# type_2_signaling.net
KiCad netlist of a schematic drawn in EAGLE
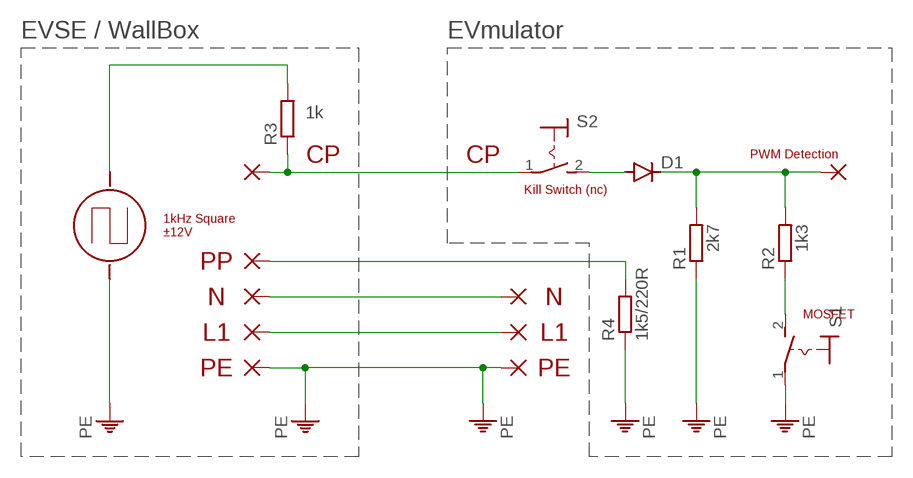
[diagram p0: schematic, sheet 1]

(export (version "E")
  (design (tool "Eeschema 10.0.6"))
  (components
    (comp (ref "D1")
      (value "OA91")
      (footprint "eagle-import:DO07")
      (libsource (lib "eagle-import") (part "OA91"))
    )
    (comp (ref "PAD1")
      (value "1,6/0,8")
      (footprint "eagle-import:1,6_0,8")
      (libsource (lib "eagle-import") (part "1,6/0,8"))
    )
    (comp (ref "PAD2")
      (value "1,6/0,8")
      (footprint "eagle-import:1,6_0,8")
      (libsource (lib "eagle-import") (part "1,6/0,8"))
    )
    (comp (ref "PAD3")
      (value "1,6/0,8")
      (footprint "eagle-import:1,6_0,8")
      (libsource (lib "eagle-import") (part "1,6/0,8"))
    )
    (comp (ref "PAD4")
      (value "1,6/0,8")
      (footprint "eagle-import:1,6_0,8")
      (libsource (lib "eagle-import") (part "1,6/0,8"))
    )
    (comp (ref "PAD5")
      (value "1,6/0,8")
      (footprint "eagle-import:1,6_0,8")
      (libsource (lib "eagle-import") (part "1,6/0,8"))
    )
    (comp (ref "PAD6")
      (value "1,6/0,8")
      (footprint "eagle-import:1,6_0,8")
      (libsource (lib "eagle-import") (part "1,6/0,8"))
    )
    (comp (ref "PAD7")
      (value "1,6/0,8")
      (footprint "eagle-import:1,6_0,8")
      (libsource (lib "eagle-import") (part "1,6/0,8"))
    )
    (comp (ref "PAD8")
      (value "1,6/0,8")
      (footprint "eagle-import:1,6_0,8")
      (libsource (lib "eagle-import") (part "1,6/0,8"))
    )
    (comp (ref "PAD9")
      (value "1,6/0,8")
      (footprint "eagle-import:1,6_0,8")
      (libsource (lib "eagle-import") (part "1,6/0,8"))
    )
    (comp (ref "R1")
      (value "2k7")
      (footprint "eagle-import:0204_7")
      (libsource (lib "eagle-import") (part "R-EU_0204/7"))
    )
    (comp (ref "R2")
      (value "1k3")
      (footprint "eagle-import:0204_7")
      (libsource (lib "eagle-import") (part "R-EU_0204/7"))
    )
    (comp (ref "R3")
      (value "1k")
      (footprint "eagle-import:0204_7")
      (libsource (lib "eagle-import") (part "R-EU_0204/7"))
    )
    (comp (ref "R4")
      (value "1k5/220R")
      (footprint "eagle-import:0204_7")
      (libsource (lib "eagle-import") (part "R-EU_0204/7"))
    )
    (comp (ref "S1")
      (value "MS243")
      (footprint "eagle-import:MS243")
      (libsource (lib "eagle-import") (part "MS243"))
    )
    (comp (ref "S2")
      (value "MS243")
      (footprint "eagle-import:MS243")
      (libsource (lib "eagle-import") (part "MS243"))
    )
  )
  (nets
    (net (code "1") (name "Net-(PAD1-P)") (class "Default")
      (node (ref "PAD1") (pin "1") (pinfunction "P_1") (pintype "passive"))
      (node (ref "R3") (pin "1") (pinfunction "1_1") (pintype "passive"))
      (node (ref "S2") (pin "1") (pinfunction "P_1") (pintype "passive"))
    )
    (net (code "2") (name "Net-(PAD2-P)") (class "Default")
      (node (ref "D1") (pin "C") (pinfunction "C_C") (pintype "passive"))
      (node (ref "PAD2") (pin "1") (pinfunction "P_1") (pintype "passive"))
      (node (ref "R1") (pin "2") (pinfunction "2_2") (pintype "passive"))
      (node (ref "R2") (pin "2") (pinfunction "2_2") (pintype "passive"))
    )
    (net (code "3") (name "Net-(PAD3-P)") (class "Default")
      (node (ref "PAD3") (pin "1") (pinfunction "P_1") (pintype "passive"))
      (node (ref "PAD5") (pin "1") (pinfunction "P_1") (pintype "passive"))
    )
    (net (code "4") (name "Net-(PAD4-P)") (class "Default")
      (node (ref "PAD4") (pin "1") (pinfunction "P_1") (pintype "passive"))
      (node (ref "PAD6") (pin "1") (pinfunction "P_1") (pintype "passive"))
    )
    (net (code "5") (name "Net-(PAD9-P)") (class "Default")
      (node (ref "PAD9") (pin "1") (pinfunction "P_1") (pintype "passive"))
      (node (ref "R4") (pin "2") (pinfunction "2_2") (pintype "passive"))
    )
    (net (code "6") (name "Net-(S1-S)") (class "Default")
      (node (ref "R2") (pin "1") (pinfunction "1_1") (pintype "passive"))
      (node (ref "S1") (pin "2") (pinfunction "S_2") (pintype "passive"))
    )
    (net (code "7") (name "Net-(S2-S)") (class "Default")
      (node (ref "D1") (pin "A") (pinfunction "A_A") (pintype "passive"))
      (node (ref "S2") (pin "2") (pinfunction "S_2") (pintype "passive"))
    )
    (net (code "8") (name "PE") (class "Default")
      (node (ref "PAD7") (pin "1") (pinfunction "P_1") (pintype "passive"))
      (node (ref "PAD8") (pin "1") (pinfunction "P_1") (pintype "passive"))
      (node (ref "R1") (pin "1") (pinfunction "1_1") (pintype "passive"))
      (node (ref "R4") (pin "1") (pinfunction "1_1") (pintype "passive"))
      (node (ref "S1") (pin "1") (pinfunction "P_1") (pintype "passive"))
    )
    (net (code "9") (name "unconnected-(R3-Pad2)") (class "Default")
      (node (ref "R3") (pin "2") (pinfunction "2_2") (pintype "passive"))
    )
  )
)
